# design.net
KiCad netlist of a schematic drawn in Altium Designer
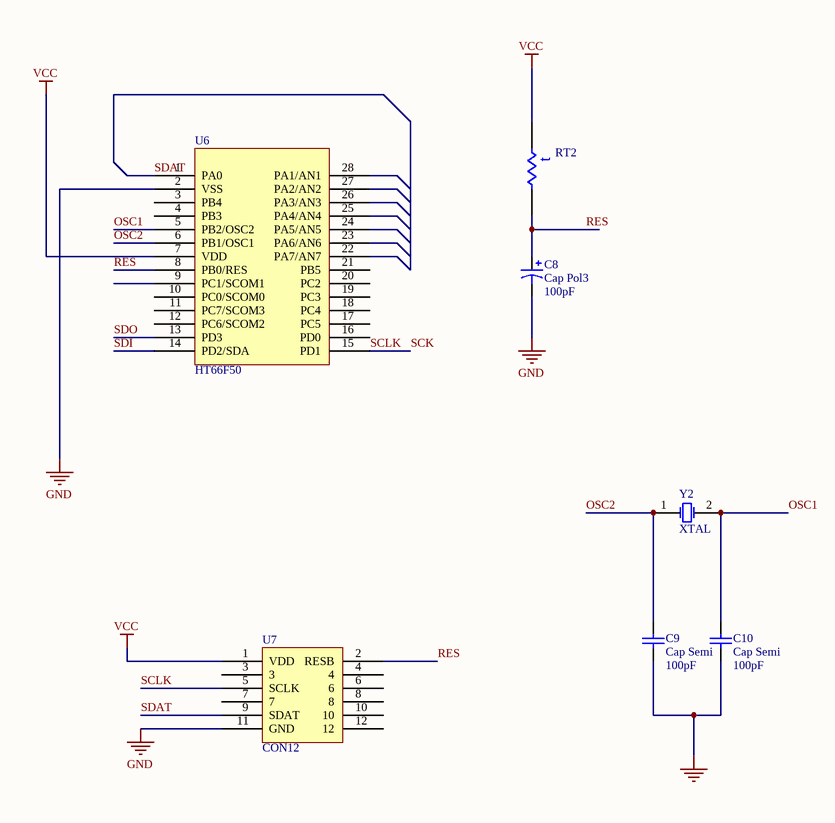
[diagram p0: 最小系统.SchDoc]

(export (version "E")
  (design (tool "Eeschema 10.0.6"))
  (components
    (comp (ref "C8")
      (value "Cap Pol3")
      (footprint "C0805")
      (description "Polarized Capacitor (Surface Mount)")
      (fields (field (name "ALTIUM_VALUE") "100pF") (field (name "PUBLISHER") "Altium Limited"))
      (libsource (lib "Miscellaneous Devices") (part "Cap Pol3"))
    )
    (comp (ref "C9")
      (value "Cap Semi")
      (footprint "1608[0603]")
      (description "Capacitor (Semiconductor SIM Model)")
      (fields (field (name "ALTIUM_VALUE") "100pF") (field (name "PUBLISHER") "Altium Limited"))
      (libsource (lib "Miscellaneous Devices") (part "Cap Semi"))
    )
    (comp (ref "C10")
      (value "Cap Semi")
      (footprint "1608[0603]")
      (description "Capacitor (Semiconductor SIM Model)")
      (fields (field (name "ALTIUM_VALUE") "100pF") (field (name "PUBLISHER") "Altium Limited"))
      (libsource (lib "Miscellaneous Devices") (part "Cap Semi"))
    )
    (comp (ref "RT2")
      (value "~")
      (footprint "6-0805")
      (description "Thermistor")
      (fields (field (name "PUBLISHER") "Altium Limited"))
      (libsource (lib "Miscellaneous Devices") (part "Res Thermal"))
    )
    (comp (ref "U6") (value "HT66F50") (footprint "DIP28") (libsource (lib "LIC") (part "HT66F50")))
    (comp (ref "U7") (value "CON12") (footprint "MHDR2X6") (libsource (lib "LIC") (part "CON12")))
    (comp (ref "Y2")
      (value "XTAL")
      (footprint "R38")
      (description "Crystal Oscillator")
      (fields (field (name "PUBLISHER") "Altium Limited"))
      (libsource (lib "Miscellaneous Devices") (part "XTAL"))
    )
  )
  (nets
    (net (code "1") (name "/OSC1") (class "Default")
      (node (ref "C10") (pin "1") (pinfunction "1_1") (pintype "passive"))
      (node (ref "U6") (pin "5") (pinfunction "PB2/OSC2_5") (pintype "passive"))
      (node (ref "Y2") (pin "2") (pinfunction "OSC2_2") (pintype "passive"))
    )
    (net (code "2") (name "/OSC2") (class "Default")
      (node (ref "C9") (pin "1") (pinfunction "1_1") (pintype "passive"))
      (node (ref "U6") (pin "6") (pinfunction "PB1/OSC1_6") (pintype "passive"))
      (node (ref "Y2") (pin "1") (pinfunction "OSC1_1") (pintype "passive"))
    )
    (net (code "3") (name "/RES") (class "Default")
      (node (ref "C8") (pin "1") (pinfunction "1_1") (pintype "passive"))
      (node (ref "RT2") (pin "2") (pinfunction "2_2") (pintype "passive"))
      (node (ref "U6") (pin "8") (pinfunction "PB0/RES_8") (pintype "passive"))
      (node (ref "U7") (pin "2") (pinfunction "RESB_2") (pintype "passive"))
    )
    (net (code "4") (name "/SCK") (class "Default")
      (node (ref "U6") (pin "15") (pinfunction "PD1_15") (pintype "passive"))
      (node (ref "U7") (pin "5") (pinfunction "SCLK_5") (pintype "passive"))
    )
    (net (code "5") (name "/SDAT") (class "Default")
      (node (ref "U6") (pin "1") (pinfunction "PA0_1") (pintype "passive"))
      (node (ref "U7") (pin "9") (pinfunction "SDAT_9") (pintype "passive"))
    )
    (net (code "6") (name "/SDI") (class "Default")
      (node (ref "U6") (pin "14") (pinfunction "PD2/SDA_14") (pintype "passive"))
    )
    (net (code "7") (name "/SDO") (class "Default")
      (node (ref "U6") (pin "13") (pinfunction "PD3_13") (pintype "passive"))
    )
    (net (code "8") (name "GND") (class "Default")
      (node (ref "C10") (pin "2") (pinfunction "2_2") (pintype "passive"))
      (node (ref "C8") (pin "2") (pinfunction "2_2") (pintype "passive"))
      (node (ref "C9") (pin "2") (pinfunction "2_2") (pintype "passive"))
      (node (ref "U6") (pin "2") (pinfunction "VSS_2") (pintype "passive"))
      (node (ref "U7") (pin "11") (pinfunction "GND_11") (pintype "passive"))
    )
    (net (code "9") (name "VCC") (class "Default")
      (node (ref "RT2") (pin "1") (pinfunction "1_1") (pintype "passive"))
      (node (ref "U6") (pin "7") (pinfunction "VDD_7") (pintype "passive"))
      (node (ref "U7") (pin "1") (pinfunction "VDD_1") (pintype "passive"))
    )
    (net (code "10") (name "unconnected-(U6-PA1{slash}AN1-Pad28)") (class "Default")
      (node (ref "U6") (pin "28") (pinfunction "PA1/AN1_28") (pintype "passive"))
    )
    (net (code "11") (name "unconnected-(U6-PA2{slash}AN2-Pad27)") (class "Default")
      (node (ref "U6") (pin "27") (pinfunction "PA2/AN2_27") (pintype "passive"))
    )
    (net (code "12") (name "unconnected-(U6-PA3{slash}AN3-Pad26)") (class "Default")
      (node (ref "U6") (pin "26") (pinfunction "PA3/AN3_26") (pintype "passive"))
    )
    (net (code "13") (name "unconnected-(U6-PA4{slash}AN4-Pad25)") (class "Default")
      (node (ref "U6") (pin "25") (pinfunction "PA4/AN4_25") (pintype "passive"))
    )
    (net (code "14") (name "unconnected-(U6-PA5{slash}AN5-Pad24)") (class "Default")
      (node (ref "U6") (pin "24") (pinfunction "PA5/AN5_24") (pintype "passive"))
    )
    (net (code "15") (name "unconnected-(U6-PA6{slash}AN6-Pad23)") (class "Default")
      (node (ref "U6") (pin "23") (pinfunction "PA6/AN6_23") (pintype "passive"))
    )
    (net (code "16") (name "unconnected-(U6-PA7{slash}AN7-Pad22)") (class "Default")
      (node (ref "U6") (pin "22") (pinfunction "PA7/AN7_22") (pintype "passive"))
    )
    (net (code "17") (name "unconnected-(U6-PB3-Pad4)") (class "Default")
      (node (ref "U6") (pin "4") (pinfunction "PB3_4") (pintype "passive"))
    )
    (net (code "18") (name "unconnected-(U6-PB4-Pad3)") (class "Default")
      (node (ref "U6") (pin "3") (pinfunction "PB4_3") (pintype "passive"))
    )
    (net (code "19") (name "unconnected-(U6-PB5-Pad21)") (class "Default")
      (node (ref "U6") (pin "21") (pinfunction "PB5_21") (pintype "passive"))
    )
    (net (code "20") (name "unconnected-(U6-PC0{slash}SCOM0-Pad10)") (class "Default")
      (node (ref "U6") (pin "10") (pinfunction "PC0/SCOM0_10") (pintype "passive"))
    )
    (net (code "21") (name "unconnected-(U6-PC1{slash}SCOM1-Pad9)") (class "Default")
      (node (ref "U6") (pin "9") (pinfunction "PC1/SCOM1_9") (pintype "passive"))
    )
    (net (code "22") (name "unconnected-(U6-PC2-Pad20)") (class "Default")
      (node (ref "U6") (pin "20") (pinfunction "PC2_20") (pintype "passive"))
    )
    (net (code "23") (name "unconnected-(U6-PC3-Pad19)") (class "Default")
      (node (ref "U6") (pin "19") (pinfunction "PC3_19") (pintype "passive"))
    )
    (net (code "24") (name "unconnected-(U6-PC4-Pad18)") (class "Default")
      (node (ref "U6") (pin "18") (pinfunction "PC4_18") (pintype "passive"))
    )
    (net (code "25") (name "unconnected-(U6-PC5-Pad17)") (class "Default")
      (node (ref "U6") (pin "17") (pinfunction "PC5_17") (pintype "passive"))
    )
    (net (code "26") (name "unconnected-(U6-PC6{slash}SCOM2-Pad12)") (class "Default")
      (node (ref "U6") (pin "12") (pinfunction "PC6/SCOM2_12") (pintype "passive"))
    )
    (net (code "27") (name "unconnected-(U6-PC7{slash}SCOM3-Pad11)") (class "Default")
      (node (ref "U6") (pin "11") (pinfunction "PC7/SCOM3_11") (pintype "passive"))
    )
    (net (code "28") (name "unconnected-(U6-PD0-Pad16)") (class "Default")
      (node (ref "U6") (pin "16") (pinfunction "PD0_16") (pintype "passive"))
    )
    (net (code "29") (name "unconnected-(U7-Pad3)") (class "Default")
      (node (ref "U7") (pin "3") (pinfunction "3_3") (pintype "passive"))
    )
    (net (code "30") (name "unconnected-(U7-Pad4)") (class "Default")
      (node (ref "U7") (pin "4") (pinfunction "4_4") (pintype "passive"))
    )
    (net (code "31") (name "unconnected-(U7-Pad6)") (class "Default")
      (node (ref "U7") (pin "6") (pinfunction "6_6") (pintype "passive"))
    )
    (net (code "32") (name "unconnected-(U7-Pad7)") (class "Default")
      (node (ref "U7") (pin "7") (pinfunction "7_7") (pintype "passive"))
    )
    (net (code "33") (name "unconnected-(U7-Pad8)") (class "Default")
      (node (ref "U7") (pin "8") (pinfunction "8_8") (pintype "passive"))
    )
    (net (code "34") (name "unconnected-(U7-Pad10)") (class "Default")
      (node (ref "U7") (pin "10") (pinfunction "10_10") (pintype "passive"))
    )
    (net (code "35") (name "unconnected-(U7-Pad12)") (class "Default")
      (node (ref "U7") (pin "12") (pinfunction "12_12") (pintype "passive"))
    )
  )
)
